# testv1.net
KiCad netlist of a schematic drawn in EAGLE
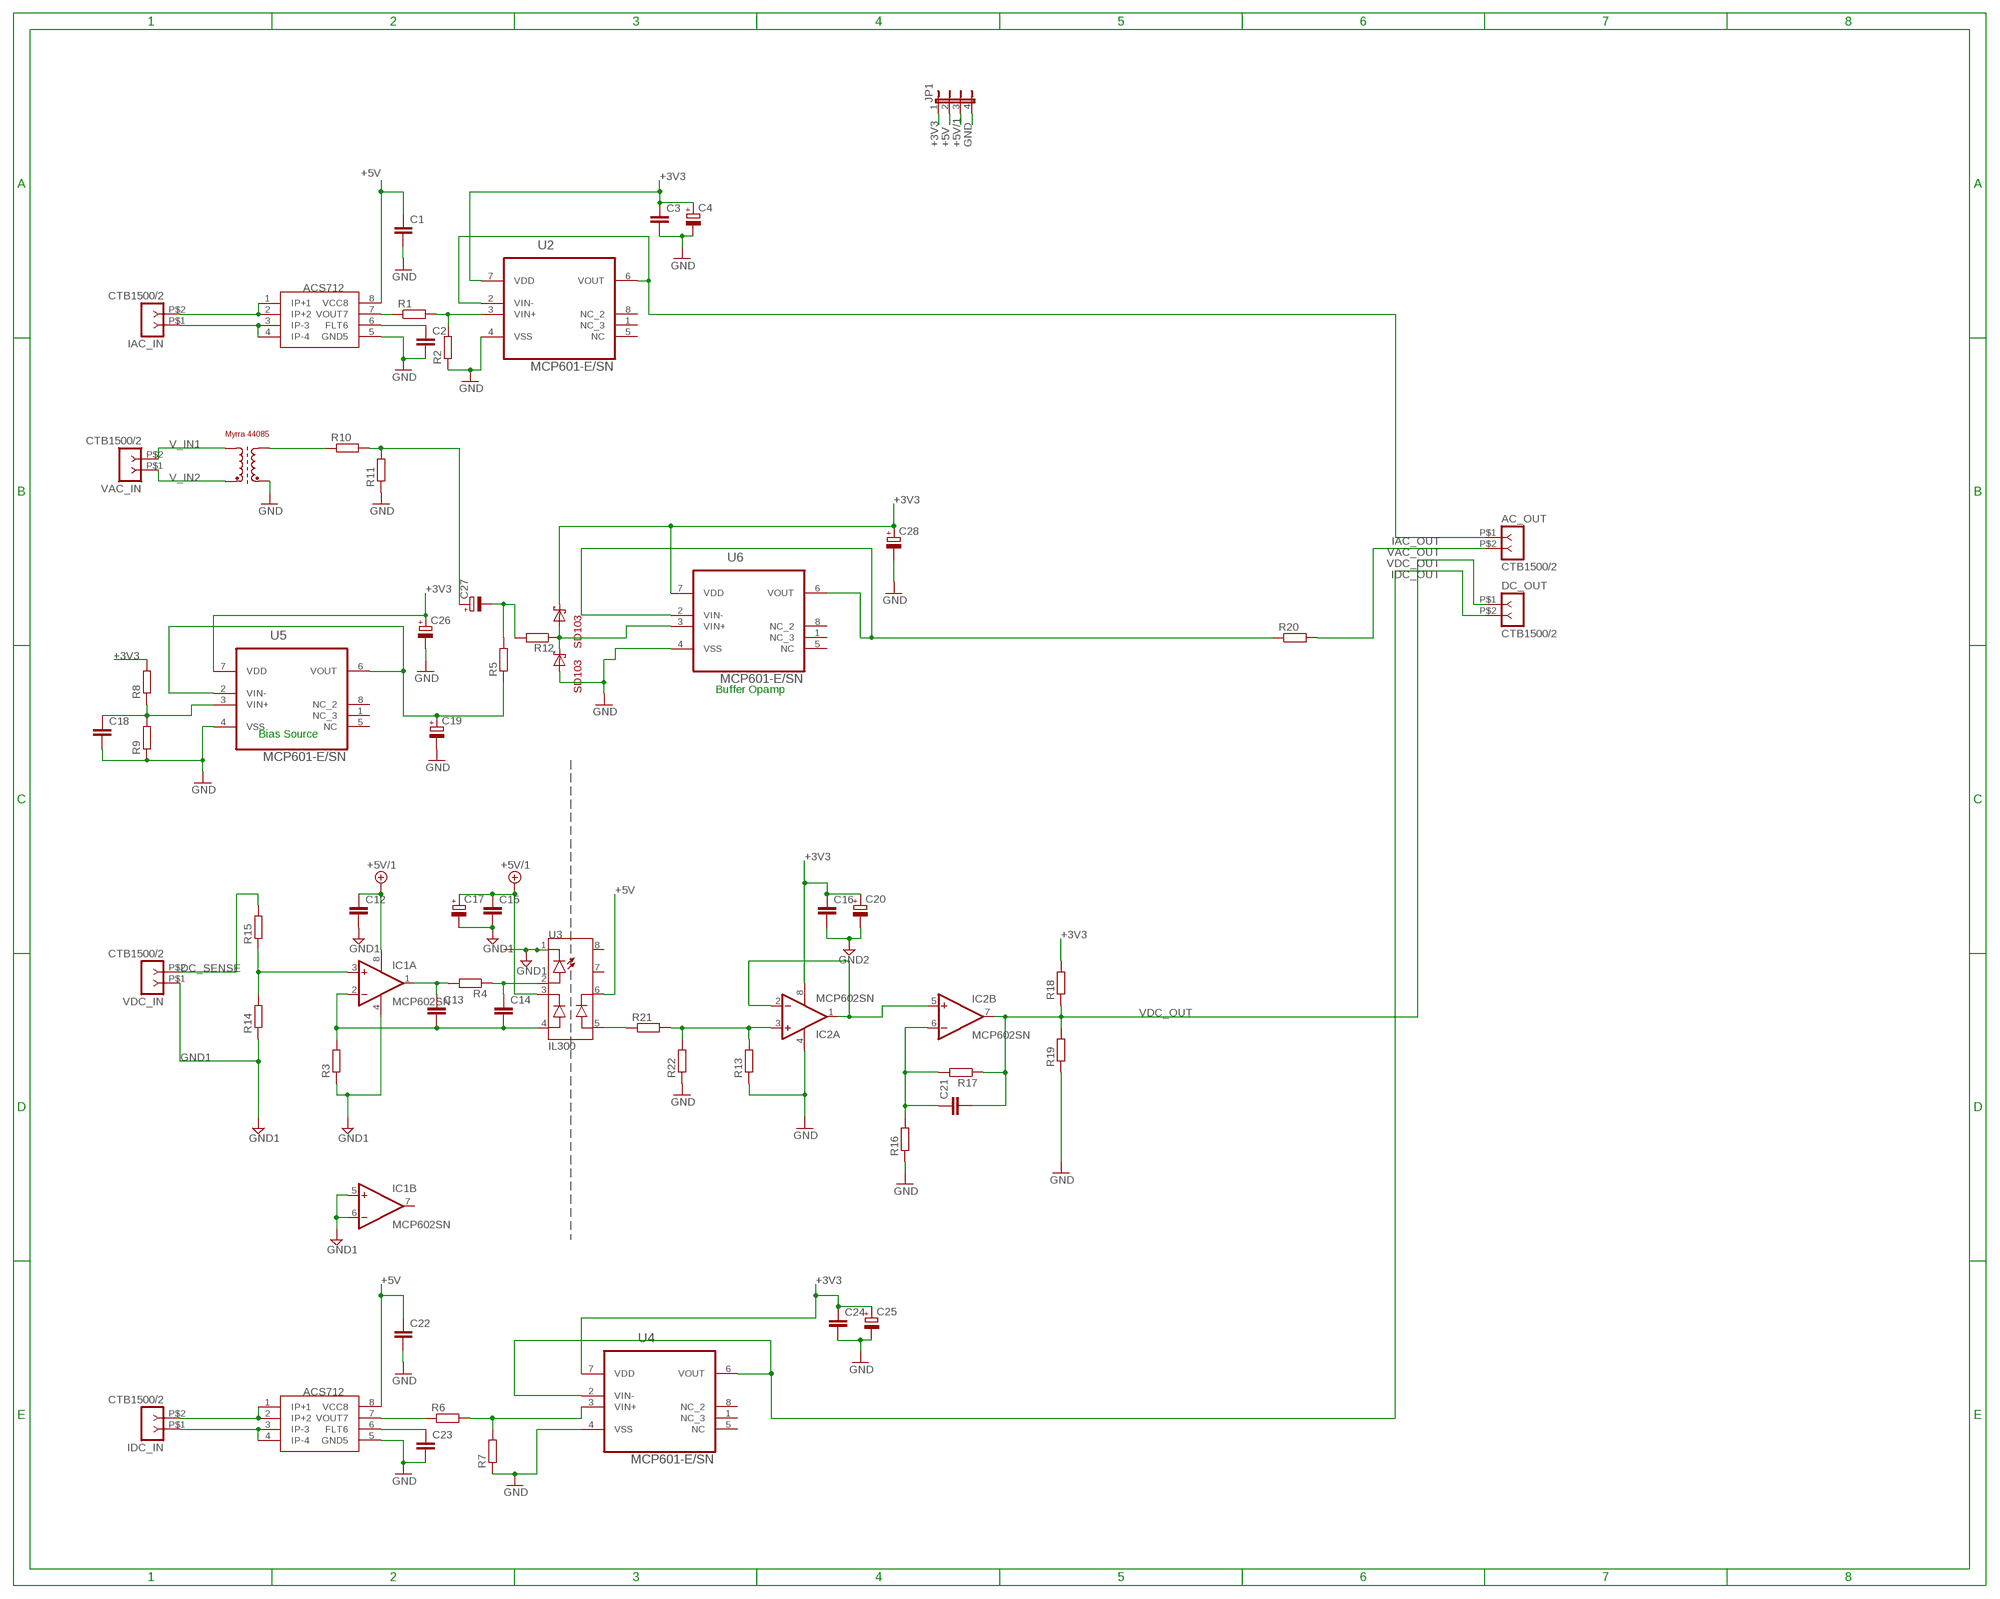
[diagram p0: schematic, sheet 1]

(export (version "E")
  (design (tool "Eeschema 10.0.6"))
  (components
    (comp (ref "AC_OUT")
      (value "CTB1500/2")
      (footprint "eagle-import:CTB1500-2")
      (libsource (lib "eagle-import") (part "CTB1500/2"))
    )
    (comp (ref "C1")
      (value "C-EU025-025X050")
      (footprint "eagle-import:C025-025X050")
      (libsource (lib "eagle-import") (part "C-EU025-025X050"))
    )
    (comp (ref "C2")
      (value "C-EU025-025X050")
      (footprint "eagle-import:C025-025X050")
      (libsource (lib "eagle-import") (part "C-EU025-025X050"))
    )
    (comp (ref "C3")
      (value "C-EU025-025X050")
      (footprint "eagle-import:C025-025X050")
      (libsource (lib "eagle-import") (part "C-EU025-025X050"))
    )
    (comp (ref "C4")
      (value "CPOL-EUE2-4")
      (footprint "eagle-import:E2-4")
      (libsource (lib "eagle-import") (part "CPOL-EUE2-4"))
    )
    (comp (ref "C12")
      (value "C-EU025-025X050")
      (footprint "eagle-import:C025-025X050")
      (libsource (lib "eagle-import") (part "C-EU025-025X050"))
    )
    (comp (ref "C13")
      (value "C-EU025-025X050")
      (footprint "eagle-import:C025-025X050")
      (libsource (lib "eagle-import") (part "C-EU025-025X050"))
    )
    (comp (ref "C14")
      (value "C-EU025-025X050")
      (footprint "eagle-import:C025-025X050")
      (libsource (lib "eagle-import") (part "C-EU025-025X050"))
    )
    (comp (ref "C15")
      (value "C-EU025-025X050")
      (footprint "eagle-import:C025-025X050")
      (libsource (lib "eagle-import") (part "C-EU025-025X050"))
    )
    (comp (ref "C16")
      (value "C-EU025-025X050")
      (footprint "eagle-import:C025-025X050")
      (libsource (lib "eagle-import") (part "C-EU025-025X050"))
    )
    (comp (ref "C17")
      (value "CPOL-EUE2-4")
      (footprint "eagle-import:E2-4")
      (libsource (lib "eagle-import") (part "CPOL-EUE2-4"))
    )
    (comp (ref "C18")
      (value "C-EU025-025X050")
      (footprint "eagle-import:C025-025X050")
      (libsource (lib "eagle-import") (part "C-EU025-025X050"))
    )
    (comp (ref "C19")
      (value "CPOL-EUE2-4")
      (footprint "eagle-import:E2-4")
      (libsource (lib "eagle-import") (part "CPOL-EUE2-4"))
    )
    (comp (ref "C20")
      (value "CPOL-EUE2-4")
      (footprint "eagle-import:E2-4")
      (libsource (lib "eagle-import") (part "CPOL-EUE2-4"))
    )
    (comp (ref "C21")
      (value "C-EU025-025X050")
      (footprint "eagle-import:C025-025X050")
      (libsource (lib "eagle-import") (part "C-EU025-025X050"))
    )
    (comp (ref "C22")
      (value "C-EU025-025X050")
      (footprint "eagle-import:C025-025X050")
      (libsource (lib "eagle-import") (part "C-EU025-025X050"))
    )
    (comp (ref "C23")
      (value "C-EU025-025X050")
      (footprint "eagle-import:C025-025X050")
      (libsource (lib "eagle-import") (part "C-EU025-025X050"))
    )
    (comp (ref "C24")
      (value "C-EU025-025X050")
      (footprint "eagle-import:C025-025X050")
      (libsource (lib "eagle-import") (part "C-EU025-025X050"))
    )
    (comp (ref "C25")
      (value "CPOL-EUE2-4")
      (footprint "eagle-import:E2-4")
      (libsource (lib "eagle-import") (part "CPOL-EUE2-4"))
    )
    (comp (ref "C26")
      (value "CPOL-EUE2-4")
      (footprint "eagle-import:E2-4")
      (libsource (lib "eagle-import") (part "CPOL-EUE2-4"))
    )
    (comp (ref "C27")
      (value "CPOL-EUE2-4")
      (footprint "eagle-import:E2-4")
      (libsource (lib "eagle-import") (part "CPOL-EUE2-4"))
    )
    (comp (ref "C28")
      (value "CPOL-EUE2-4")
      (footprint "eagle-import:E2-4")
      (libsource (lib "eagle-import") (part "CPOL-EUE2-4"))
    )
    (comp (ref "DC_OUT")
      (value "CTB1500/2")
      (footprint "eagle-import:CTB1500-2")
      (libsource (lib "eagle-import") (part "CTB1500/2"))
    )
    (comp (ref "IAC_IN")
      (value "CTB1500/2")
      (footprint "eagle-import:CTB1500-2")
      (libsource (lib "eagle-import") (part "CTB1500/2"))
    )
    (comp (ref "IC1")
      (value "MCP602SN")
      (footprint "eagle-import:SO08")
      (libsource (lib "eagle-import") (part "MCP602SN"))
    )
    (comp (ref "IC2")
      (value "MCP602SN")
      (footprint "eagle-import:SO08")
      (libsource (lib "eagle-import") (part "MCP602SN"))
    )
    (comp (ref "IDC_IN")
      (value "CTB1500/2")
      (footprint "eagle-import:CTB1500-2")
      (libsource (lib "eagle-import") (part "CTB1500/2"))
    )
    (comp (ref "JP1")
      (value "JP4E")
      (footprint "eagle-import:JP4")
      (libsource (lib "eagle-import") (part "JP4E"))
    )
    (comp (ref "R1")
      (value "R-EU_0207/7")
      (footprint "eagle-import:0207_7")
      (libsource (lib "eagle-import") (part "R-EU_0207/7"))
    )
    (comp (ref "R2")
      (value "R-EU_0207/7")
      (footprint "eagle-import:0207_7")
      (libsource (lib "eagle-import") (part "R-EU_0207/7"))
    )
    (comp (ref "R3")
      (value "R-EU_0207/7")
      (footprint "eagle-import:0207_7")
      (libsource (lib "eagle-import") (part "R-EU_0207/7"))
    )
    (comp (ref "R4")
      (value "R-EU_0207/7")
      (footprint "eagle-import:0207_7")
      (libsource (lib "eagle-import") (part "R-EU_0207/7"))
    )
    (comp (ref "R5")
      (value "R-EU_0207/7")
      (footprint "eagle-import:0207_7")
      (libsource (lib "eagle-import") (part "R-EU_0207/7"))
    )
    (comp (ref "R6")
      (value "R-EU_0207/7")
      (footprint "eagle-import:0207_7")
      (libsource (lib "eagle-import") (part "R-EU_0207/7"))
    )
    (comp (ref "R7")
      (value "R-EU_0207/7")
      (footprint "eagle-import:0207_7")
      (libsource (lib "eagle-import") (part "R-EU_0207/7"))
    )
    (comp (ref "R8")
      (value "R-EU_0207/7")
      (footprint "eagle-import:0207_7")
      (libsource (lib "eagle-import") (part "R-EU_0207/7"))
    )
    (comp (ref "R9")
      (value "R-EU_0207/7")
      (footprint "eagle-import:0207_7")
      (libsource (lib "eagle-import") (part "R-EU_0207/7"))
    )
    (comp (ref "R10")
      (value "R-EU_0207/7")
      (footprint "eagle-import:0207_7")
      (libsource (lib "eagle-import") (part "R-EU_0207/7"))
    )
    (comp (ref "R11")
      (value "R-EU_0207/7")
      (footprint "eagle-import:0207_7")
      (libsource (lib "eagle-import") (part "R-EU_0207/7"))
    )
    (comp (ref "R12")
      (value "R-EU_0207/7")
      (footprint "eagle-import:0207_7")
      (libsource (lib "eagle-import") (part "R-EU_0207/7"))
    )
    (comp (ref "R13")
      (value "R-EU_0207/7")
      (footprint "eagle-import:0207_7")
      (libsource (lib "eagle-import") (part "R-EU_0207/7"))
    )
    (comp (ref "R14")
      (value "R-EU_0207/7")
      (footprint "eagle-import:0207_7")
      (libsource (lib "eagle-import") (part "R-EU_0207/7"))
    )
    (comp (ref "R15")
      (value "R-EU_0207/7")
      (footprint "eagle-import:0207_7")
      (libsource (lib "eagle-import") (part "R-EU_0207/7"))
    )
    (comp (ref "R16")
      (value "R-EU_0207/7")
      (footprint "eagle-import:0207_7")
      (libsource (lib "eagle-import") (part "R-EU_0207/7"))
    )
    (comp (ref "R17")
      (value "R-EU_0207/7")
      (footprint "eagle-import:0207_7")
      (libsource (lib "eagle-import") (part "R-EU_0207/7"))
    )
    (comp (ref "R18")
      (value "R-EU_0207/7")
      (footprint "eagle-import:0207_7")
      (libsource (lib "eagle-import") (part "R-EU_0207/7"))
    )
    (comp (ref "R19")
      (value "R-EU_0207/7")
      (footprint "eagle-import:0207_7")
      (libsource (lib "eagle-import") (part "R-EU_0207/7"))
    )
    (comp (ref "R20")
      (value "R-EU_0207/7")
      (footprint "eagle-import:0207_7")
      (libsource (lib "eagle-import") (part "R-EU_0207/7"))
    )
    (comp (ref "R21")
      (value "R-EU_0207/7")
      (footprint "eagle-import:0207_7")
      (libsource (lib "eagle-import") (part "R-EU_0207/7"))
    )
    (comp (ref "R22")
      (value "R-EU_0207/7")
      (footprint "eagle-import:0207_7")
      (libsource (lib "eagle-import") (part "R-EU_0207/7"))
    )
    (comp (ref "U$1")
      (value "ACS712")
      (footprint "eagle-import:SOIC8")
      (libsource (lib "eagle-import") (part "ACS712"))
    )
    (comp (ref "U$6")
      (value "MYRRA_4408")
      (footprint "eagle-import:4408")
      (libsource (lib "eagle-import") (part "MYRRA_4408"))
    )
    (comp (ref "U$7")
      (value "SD103A")
      (footprint "eagle-import:D035-10")
      (libsource (lib "eagle-import") (part "SD103A"))
    )
    (comp (ref "U$8")
      (value "SD103A")
      (footprint "eagle-import:D035-10")
      (libsource (lib "eagle-import") (part "SD103A"))
    )
    (comp (ref "U$10")
      (value "ACS712")
      (footprint "eagle-import:SOIC8")
      (libsource (lib "eagle-import") (part "ACS712"))
    )
    (comp (ref "U2")
      (value "MCP601-E/SN")
      (footprint "eagle-import:SOIC127P600X175-8N")
      (libsource (lib "eagle-import") (part "MCP601-E/SN"))
    )
    (comp (ref "U3")
      (value "IL300")
      (footprint "eagle-import:SO8")
      (libsource (lib "eagle-import") (part "IL300"))
    )
    (comp (ref "U4")
      (value "MCP601-E/SN")
      (footprint "eagle-import:SOIC127P600X175-8N")
      (libsource (lib "eagle-import") (part "MCP601-E/SN"))
    )
    (comp (ref "U5")
      (value "MCP601-E/SN")
      (footprint "eagle-import:SOIC127P600X175-8N")
      (libsource (lib "eagle-import") (part "MCP601-E/SN"))
    )
    (comp (ref "U6")
      (value "MCP601-E/SN")
      (footprint "eagle-import:SOIC127P600X175-8N")
      (libsource (lib "eagle-import") (part "MCP601-E/SN"))
    )
    (comp (ref "VAC_IN")
      (value "CTB1500/2")
      (footprint "eagle-import:CTB1500-2")
      (libsource (lib "eagle-import") (part "CTB1500/2"))
    )
    (comp (ref "VDC_IN")
      (value "CTB1500/2")
      (footprint "eagle-import:CTB1500-2")
      (libsource (lib "eagle-import") (part "CTB1500/2"))
    )
  )
  (nets
    (net (code "1") (name "+5V{slash}1") (class "Default")
      (node (ref "C12") (pin "1") (pinfunction "1_1") (pintype "passive"))
      (node (ref "C15") (pin "1") (pinfunction "1_1") (pintype "passive"))
      (node (ref "C17") (pin "+") (pinfunction "+_+") (pintype "passive"))
      (node (ref "IC1") (pin "8") (pinfunction "V+_8") (pintype "power_in"))
      (node (ref "JP1") (pin "3") (pinfunction "3_3") (pintype "passive"))
      (node (ref "U3") (pin "3") (pinfunction "C_FB_3") (pintype "passive"))
    )
    (net (code "2") (name "/+3V3") (class "Default")
      (node (ref "C16") (pin "1") (pinfunction "1_1") (pintype "passive"))
      (node (ref "C20") (pin "+") (pinfunction "+_+") (pintype "passive"))
      (node (ref "C24") (pin "1") (pinfunction "1_1") (pintype "passive"))
      (node (ref "C25") (pin "+") (pinfunction "+_+") (pintype "passive"))
      (node (ref "C26") (pin "+") (pinfunction "+_+") (pintype "passive"))
      (node (ref "C28") (pin "+") (pinfunction "+_+") (pintype "passive"))
      (node (ref "C3") (pin "1") (pinfunction "1_1") (pintype "passive"))
      (node (ref "C4") (pin "+") (pinfunction "+_+") (pintype "passive"))
      (node (ref "IC2") (pin "8") (pinfunction "V+_8") (pintype "power_in"))
      (node (ref "JP1") (pin "1") (pinfunction "1_1") (pintype "passive"))
      (node (ref "R18") (pin "2") (pinfunction "2_2") (pintype "passive"))
      (node (ref "R8") (pin "2") (pinfunction "2_2") (pintype "passive"))
      (node (ref "U$7") (pin "C") (pinfunction "C_C") (pintype "passive"))
      (node (ref "U2") (pin "7") (pinfunction "VDD_7") (pintype "power_in"))
      (node (ref "U4") (pin "7") (pinfunction "VDD_7") (pintype "power_in"))
      (node (ref "U5") (pin "7") (pinfunction "VDD_7") (pintype "power_in"))
      (node (ref "U6") (pin "7") (pinfunction "VDD_7") (pintype "power_in"))
    )
    (net (code "3") (name "/+5V") (class "Default")
      (node (ref "C1") (pin "1") (pinfunction "1_1") (pintype "passive"))
      (node (ref "C22") (pin "1") (pinfunction "1_1") (pintype "passive"))
      (node (ref "JP1") (pin "2") (pinfunction "2_2") (pintype "passive"))
      (node (ref "U$1") (pin "8") (pinfunction "VCC8_8") (pintype "power_in"))
      (node (ref "U$10") (pin "8") (pinfunction "VCC8_8") (pintype "power_in"))
      (node (ref "U3") (pin "6") (pinfunction "C_OUT_6") (pintype "passive"))
    )
    (net (code "4") (name "/DC_SENSE") (class "Default")
      (node (ref "R15") (pin "2") (pinfunction "2_2") (pintype "passive"))
      (node (ref "VDC_IN") (pin "P$2") (pinfunction "2_P$2") (pintype "passive"))
    )
    (net (code "5") (name "/IAC_OUT") (class "Default")
      (node (ref "AC_OUT") (pin "P$1") (pinfunction "1_P$1") (pintype "passive"))
      (node (ref "U2") (pin "2") (pinfunction "VIN-_2") (pintype "input"))
      (node (ref "U2") (pin "6") (pinfunction "VOUT_6") (pintype "output"))
    )
    (net (code "6") (name "/IDC_OUT") (class "Default")
      (node (ref "DC_OUT") (pin "P$2") (pinfunction "2_P$2") (pintype "passive"))
      (node (ref "U4") (pin "2") (pinfunction "VIN-_2") (pintype "input"))
      (node (ref "U4") (pin "6") (pinfunction "VOUT_6") (pintype "output"))
    )
    (net (code "7") (name "/VAC_OUT") (class "Default")
      (node (ref "AC_OUT") (pin "P$2") (pinfunction "2_P$2") (pintype "passive"))
      (node (ref "R20") (pin "2") (pinfunction "2_2") (pintype "passive"))
    )
    (net (code "8") (name "/VDC_OUT") (class "Default")
      (node (ref "C21") (pin "2") (pinfunction "2_2") (pintype "passive"))
      (node (ref "DC_OUT") (pin "P$1") (pinfunction "1_P$1") (pintype "passive"))
      (node (ref "IC2") (pin "7") (pinfunction "OUT_7") (pintype "output"))
      (node (ref "R17") (pin "1") (pinfunction "1_1") (pintype "passive"))
      (node (ref "R18") (pin "1") (pinfunction "1_1") (pintype "passive"))
      (node (ref "R19") (pin "2") (pinfunction "2_2") (pintype "passive"))
    )
    (net (code "9") (name "/V_IN1") (class "Default")
      (node (ref "U$6") (pin "PIN5") (pinfunction "A1_PIN5") (pintype "passive"))
      (node (ref "VAC_IN") (pin "P$2") (pinfunction "2_P$2") (pintype "passive"))
    )
    (net (code "10") (name "/V_IN2") (class "Default")
      (node (ref "U$6") (pin "PIN1") (pinfunction "E1_PIN1") (pintype "passive"))
      (node (ref "VAC_IN") (pin "P$1") (pinfunction "1_P$1") (pintype "passive"))
    )
    (net (code "11") (name "GND") (class "Default")
      (node (ref "C1") (pin "2") (pinfunction "2_2") (pintype "passive"))
      (node (ref "C18") (pin "2") (pinfunction "2_2") (pintype "passive"))
      (node (ref "C19") (pin "-") (pinfunction "-_-") (pintype "passive"))
      (node (ref "C2") (pin "2") (pinfunction "2_2") (pintype "passive"))
      (node (ref "C22") (pin "2") (pinfunction "2_2") (pintype "passive"))
      (node (ref "C23") (pin "2") (pinfunction "2_2") (pintype "passive"))
      (node (ref "C24") (pin "2") (pinfunction "2_2") (pintype "passive"))
      (node (ref "C25") (pin "-") (pinfunction "-_-") (pintype "passive"))
      (node (ref "C26") (pin "-") (pinfunction "-_-") (pintype "passive"))
      (node (ref "C28") (pin "-") (pinfunction "-_-") (pintype "passive"))
      (node (ref "C3") (pin "2") (pinfunction "2_2") (pintype "passive"))
      (node (ref "C4") (pin "-") (pinfunction "-_-") (pintype "passive"))
      (node (ref "IC2") (pin "4") (pinfunction "V-_4") (pintype "power_in"))
      (node (ref "JP1") (pin "4") (pinfunction "4_4") (pintype "passive"))
      (node (ref "R11") (pin "1") (pinfunction "1_1") (pintype "passive"))
      (node (ref "R13") (pin "1") (pinfunction "1_1") (pintype "passive"))
      (node (ref "R16") (pin "1") (pinfunction "1_1") (pintype "passive"))
      (node (ref "R19") (pin "1") (pinfunction "1_1") (pintype "passive"))
      (node (ref "R2") (pin "1") (pinfunction "1_1") (pintype "passive"))
      (node (ref "R22") (pin "1") (pinfunction "1_1") (pintype "passive"))
      (node (ref "R7") (pin "1") (pinfunction "1_1") (pintype "passive"))
      (node (ref "R9") (pin "1") (pinfunction "1_1") (pintype "passive"))
      (node (ref "U$1") (pin "5") (pinfunction "GND5_5") (pintype "power_in"))
      (node (ref "U$10") (pin "5") (pinfunction "GND5_5") (pintype "power_in"))
      (node (ref "U$6") (pin "PIN9") (pinfunction "E2_PIN9") (pintype "passive"))
      (node (ref "U$8") (pin "A") (pinfunction "A_A") (pintype "passive"))
      (node (ref "U2") (pin "4") (pinfunction "VSS_4") (pintype "power_in"))
      (node (ref "U4") (pin "4") (pinfunction "VSS_4") (pintype "power_in"))
      (node (ref "U5") (pin "4") (pinfunction "VSS_4") (pintype "power_in"))
      (node (ref "U6") (pin "4") (pinfunction "VSS_4") (pintype "power_in"))
    )
    (net (code "12") (name "GND1") (class "Default")
      (node (ref "C12") (pin "2") (pinfunction "2_2") (pintype "passive"))
      (node (ref "C15") (pin "2") (pinfunction "2_2") (pintype "passive"))
      (node (ref "C17") (pin "-") (pinfunction "-_-") (pintype "passive"))
      (node (ref "IC1") (pin "4") (pinfunction "V-_4") (pintype "power_in"))
      (node (ref "IC1") (pin "5") (pinfunction "+IN_5") (pintype "input"))
      (node (ref "IC1") (pin "6") (pinfunction "-IN_6") (pintype "input"))
      (node (ref "R14") (pin "1") (pinfunction "1_1") (pintype "passive"))
      (node (ref "R3") (pin "1") (pinfunction "1_1") (pintype "passive"))
      (node (ref "U3") (pin "1") (pinfunction "C_LED_1") (pintype "passive"))
      (node (ref "VDC_IN") (pin "P$1") (pinfunction "1_P$1") (pintype "passive"))
    )
    (net (code "13") (name "GND2") (class "Default")
      (node (ref "C16") (pin "2") (pinfunction "2_2") (pintype "passive"))
      (node (ref "C20") (pin "-") (pinfunction "-_-") (pintype "passive"))
    )
    (net (code "14") (name "Net-(C27-Pad+)") (class "Default")
      (node (ref "C27") (pin "+") (pinfunction "+_+") (pintype "passive"))
      (node (ref "R10") (pin "2") (pinfunction "2_2") (pintype "passive"))
      (node (ref "R11") (pin "2") (pinfunction "2_2") (pintype "passive"))
    )
    (net (code "15") (name "Net-(C27-Pad-)") (class "Default")
      (node (ref "C27") (pin "-") (pinfunction "-_-") (pintype "passive"))
      (node (ref "R12") (pin "2") (pinfunction "2_2") (pintype "passive"))
      (node (ref "R5") (pin "2") (pinfunction "2_2") (pintype "passive"))
    )
    (net (code "16") (name "Net-(IAC_IN-1)") (class "Default")
      (node (ref "IAC_IN") (pin "P$1") (pinfunction "1_P$1") (pintype "passive"))
      (node (ref "U$1") (pin "3") (pinfunction "IP-3_3") (pintype "bidirectional"))
      (node (ref "U$1") (pin "4") (pinfunction "IP-4_4") (pintype "bidirectional"))
    )
    (net (code "17") (name "Net-(IAC_IN-2)") (class "Default")
      (node (ref "IAC_IN") (pin "P$2") (pinfunction "2_P$2") (pintype "passive"))
      (node (ref "U$1") (pin "1") (pinfunction "IP+1_1") (pintype "bidirectional"))
      (node (ref "U$1") (pin "2") (pinfunction "IP+2_2") (pintype "bidirectional"))
    )
    (net (code "18") (name "Net-(IC1A-+IN)") (class "Default")
      (node (ref "IC1") (pin "3") (pinfunction "+IN_3") (pintype "input"))
      (node (ref "R14") (pin "2") (pinfunction "2_2") (pintype "passive"))
      (node (ref "R15") (pin "1") (pinfunction "1_1") (pintype "passive"))
    )
    (net (code "19") (name "Net-(IC1A--IN)") (class "Default")
      (node (ref "C13") (pin "2") (pinfunction "2_2") (pintype "passive"))
      (node (ref "C14") (pin "2") (pinfunction "2_2") (pintype "passive"))
      (node (ref "IC1") (pin "2") (pinfunction "-IN_2") (pintype "input"))
      (node (ref "R3") (pin "2") (pinfunction "2_2") (pintype "passive"))
      (node (ref "U3") (pin "4") (pinfunction "A_FB_4") (pintype "passive"))
    )
    (net (code "20") (name "Net-(IC1A-OUT)") (class "Default")
      (node (ref "C13") (pin "1") (pinfunction "1_1") (pintype "passive"))
      (node (ref "IC1") (pin "1") (pinfunction "OUT_1") (pintype "output"))
      (node (ref "R4") (pin "2") (pinfunction "2_2") (pintype "passive"))
    )
    (net (code "21") (name "Net-(IC2A-+IN)") (class "Default")
      (node (ref "IC2") (pin "3") (pinfunction "+IN_3") (pintype "input"))
      (node (ref "R13") (pin "2") (pinfunction "2_2") (pintype "passive"))
      (node (ref "R21") (pin "2") (pinfunction "2_2") (pintype "passive"))
      (node (ref "R22") (pin "2") (pinfunction "2_2") (pintype "passive"))
    )
    (net (code "22") (name "Net-(IC2A--IN)") (class "Default")
      (node (ref "IC2") (pin "1") (pinfunction "OUT_1") (pintype "output"))
      (node (ref "IC2") (pin "2") (pinfunction "-IN_2") (pintype "input"))
      (node (ref "IC2") (pin "5") (pinfunction "+IN_5") (pintype "input"))
    )
    (net (code "23") (name "Net-(IC2B--IN)") (class "Default")
      (node (ref "C21") (pin "1") (pinfunction "1_1") (pintype "passive"))
      (node (ref "IC2") (pin "6") (pinfunction "-IN_6") (pintype "input"))
      (node (ref "R16") (pin "2") (pinfunction "2_2") (pintype "passive"))
      (node (ref "R17") (pin "2") (pinfunction "2_2") (pintype "passive"))
    )
    (net (code "24") (name "Net-(IDC_IN-1)") (class "Default")
      (node (ref "IDC_IN") (pin "P$1") (pinfunction "1_P$1") (pintype "passive"))
      (node (ref "U$10") (pin "3") (pinfunction "IP-3_3") (pintype "bidirectional"))
      (node (ref "U$10") (pin "4") (pinfunction "IP-4_4") (pintype "bidirectional"))
    )
    (net (code "25") (name "Net-(IDC_IN-2)") (class "Default")
      (node (ref "IDC_IN") (pin "P$2") (pinfunction "2_P$2") (pintype "passive"))
      (node (ref "U$10") (pin "1") (pinfunction "IP+1_1") (pintype "bidirectional"))
      (node (ref "U$10") (pin "2") (pinfunction "IP+2_2") (pintype "bidirectional"))
    )
    (net (code "26") (name "Net-(U$1-FLT6)") (class "Default")
      (node (ref "C2") (pin "1") (pinfunction "1_1") (pintype "passive"))
      (node (ref "U$1") (pin "6") (pinfunction "FLT6_6") (pintype "passive"))
    )
    (net (code "27") (name "Net-(U$1-VOUT7)") (class "Default")
      (node (ref "R1") (pin "1") (pinfunction "1_1") (pintype "passive"))
      (node (ref "U$1") (pin "7") (pinfunction "VOUT7_7") (pintype "output"))
    )
    (net (code "28") (name "Net-(U$6-A2)") (class "Default")
      (node (ref "R10") (pin "1") (pinfunction "1_1") (pintype "passive"))
      (node (ref "U$6") (pin "PIN7") (pinfunction "A2_PIN7") (pintype "passive"))
    )
    (net (code "29") (name "Net-(U$10-FLT6)") (class "Default")
      (node (ref "C23") (pin "1") (pinfunction "1_1") (pintype "passive"))
      (node (ref "U$10") (pin "6") (pinfunction "FLT6_6") (pintype "passive"))
    )
    (net (code "30") (name "Net-(U$10-VOUT7)") (class "Default")
      (node (ref "R6") (pin "1") (pinfunction "1_1") (pintype "passive"))
      (node (ref "U$10") (pin "7") (pinfunction "VOUT7_7") (pintype "output"))
    )
    (net (code "31") (name "Net-(U2-VIN+)") (class "Default")
      (node (ref "R1") (pin "2") (pinfunction "2_2") (pintype "passive"))
      (node (ref "R2") (pin "2") (pinfunction "2_2") (pintype "passive"))
      (node (ref "U2") (pin "3") (pinfunction "VIN+_3") (pintype "input"))
    )
    (net (code "32") (name "Net-(U3-A_LED)") (class "Default")
      (node (ref "C14") (pin "1") (pinfunction "1_1") (pintype "passive"))
      (node (ref "R4") (pin "1") (pinfunction "1_1") (pintype "passive"))
      (node (ref "U3") (pin "2") (pinfunction "A_LED_2") (pintype "passive"))
    )
    (net (code "33") (name "Net-(U3-A_OUT)") (class "Default")
      (node (ref "R21") (pin "1") (pinfunction "1_1") (pintype "passive"))
      (node (ref "U3") (pin "5") (pinfunction "A_OUT_5") (pintype "passive"))
    )
    (net (code "34") (name "Net-(U4-VIN+)") (class "Default")
      (node (ref "R6") (pin "2") (pinfunction "2_2") (pintype "passive"))
      (node (ref "R7") (pin "2") (pinfunction "2_2") (pintype "passive"))
      (node (ref "U4") (pin "3") (pinfunction "VIN+_3") (pintype "input"))
    )
    (net (code "35") (name "Net-(U5-VIN+)") (class "Default")
      (node (ref "C18") (pin "1") (pinfunction "1_1") (pintype "passive"))
      (node (ref "R8") (pin "1") (pinfunction "1_1") (pintype "passive"))
      (node (ref "R9") (pin "2") (pinfunction "2_2") (pintype "passive"))
      (node (ref "U5") (pin "3") (pinfunction "VIN+_3") (pintype "input"))
    )
    (net (code "36") (name "Net-(U5-VIN-)") (class "Default")
      (node (ref "C19") (pin "+") (pinfunction "+_+") (pintype "passive"))
      (node (ref "R5") (pin "1") (pinfunction "1_1") (pintype "passive"))
      (node (ref "U5") (pin "2") (pinfunction "VIN-_2") (pintype "input"))
      (node (ref "U5") (pin "6") (pinfunction "VOUT_6") (pintype "output"))
    )
    (net (code "37") (name "Net-(U6-VIN+)") (class "Default")
      (node (ref "R12") (pin "1") (pinfunction "1_1") (pintype "passive"))
      (node (ref "U$7") (pin "A") (pinfunction "A_A") (pintype "passive"))
      (node (ref "U$8") (pin "C") (pinfunction "C_C") (pintype "passive"))
      (node (ref "U6") (pin "3") (pinfunction "VIN+_3") (pintype "input"))
    )
    (net (code "38") (name "Net-(U6-VIN-)") (class "Default")
      (node (ref "R20") (pin "1") (pinfunction "1_1") (pintype "passive"))
      (node (ref "U6") (pin "2") (pinfunction "VIN-_2") (pintype "input"))
      (node (ref "U6") (pin "6") (pinfunction "VOUT_6") (pintype "output"))
    )
    (net (code "39") (name "unconnected-(IC1B-OUT-Pad7)") (class "Default")
      (node (ref "IC1") (pin "7") (pinfunction "OUT_7") (pintype "output"))
    )
    (net (code "40") (name "unconnected-(U2-NC-Pad5)") (class "Default")
      (node (ref "U2") (pin "5") (pinfunction "NC_5") (pintype "no_connect"))
    )
    (net (code "41") (name "unconnected-(U2-NC_2-Pad8)") (class "Default")
      (node (ref "U2") (pin "8") (pinfunction "NC_2_8") (pintype "no_connect"))
    )
    (net (code "42") (name "unconnected-(U2-NC_3-Pad1)") (class "Default")
      (node (ref "U2") (pin "1") (pinfunction "NC_3_1") (pintype "no_connect"))
    )
    (net (code "43") (name "unconnected-(U3-PIN7-Pad7)") (class "Default")
      (node (ref "U3") (pin "7") (pinfunction "PIN7_7") (pintype "no_connect"))
    )
    (net (code "44") (name "unconnected-(U3-PIN8-Pad8)") (class "Default")
      (node (ref "U3") (pin "8") (pinfunction "PIN8_8") (pintype "no_connect"))
    )
    (net (code "45") (name "unconnected-(U4-NC-Pad5)") (class "Default")
      (node (ref "U4") (pin "5") (pinfunction "NC_5") (pintype "no_connect"))
    )
    (net (code "46") (name "unconnected-(U4-NC_2-Pad8)") (class "Default")
      (node (ref "U4") (pin "8") (pinfunction "NC_2_8") (pintype "no_connect"))
    )
    (net (code "47") (name "unconnected-(U4-NC_3-Pad1)") (class "Default")
      (node (ref "U4") (pin "1") (pinfunction "NC_3_1") (pintype "no_connect"))
    )
    (net (code "48") (name "unconnected-(U5-NC-Pad5)") (class "Default")
      (node (ref "U5") (pin "5") (pinfunction "NC_5") (pintype "no_connect"))
    )
    (net (code "49") (name "unconnected-(U5-NC_2-Pad8)") (class "Default")
      (node (ref "U5") (pin "8") (pinfunction "NC_2_8") (pintype "no_connect"))
    )
    (net (code "50") (name "unconnected-(U5-NC_3-Pad1)") (class "Default")
      (node (ref "U5") (pin "1") (pinfunction "NC_3_1") (pintype "no_connect"))
    )
    (net (code "51") (name "unconnected-(U6-NC-Pad5)") (class "Default")
      (node (ref "U6") (pin "5") (pinfunction "NC_5") (pintype "no_connect"))
    )
    (net (code "52") (name "unconnected-(U6-NC_2-Pad8)") (class "Default")
      (node (ref "U6") (pin "8") (pinfunction "NC_2_8") (pintype "no_connect"))
    )
    (net (code "53") (name "unconnected-(U6-NC_3-Pad1)") (class "Default")
      (node (ref "U6") (pin "1") (pinfunction "NC_3_1") (pintype "no_connect"))
    )
  )
)
